# transmitter.net
KiCad netlist of a schematic drawn in EAGLE
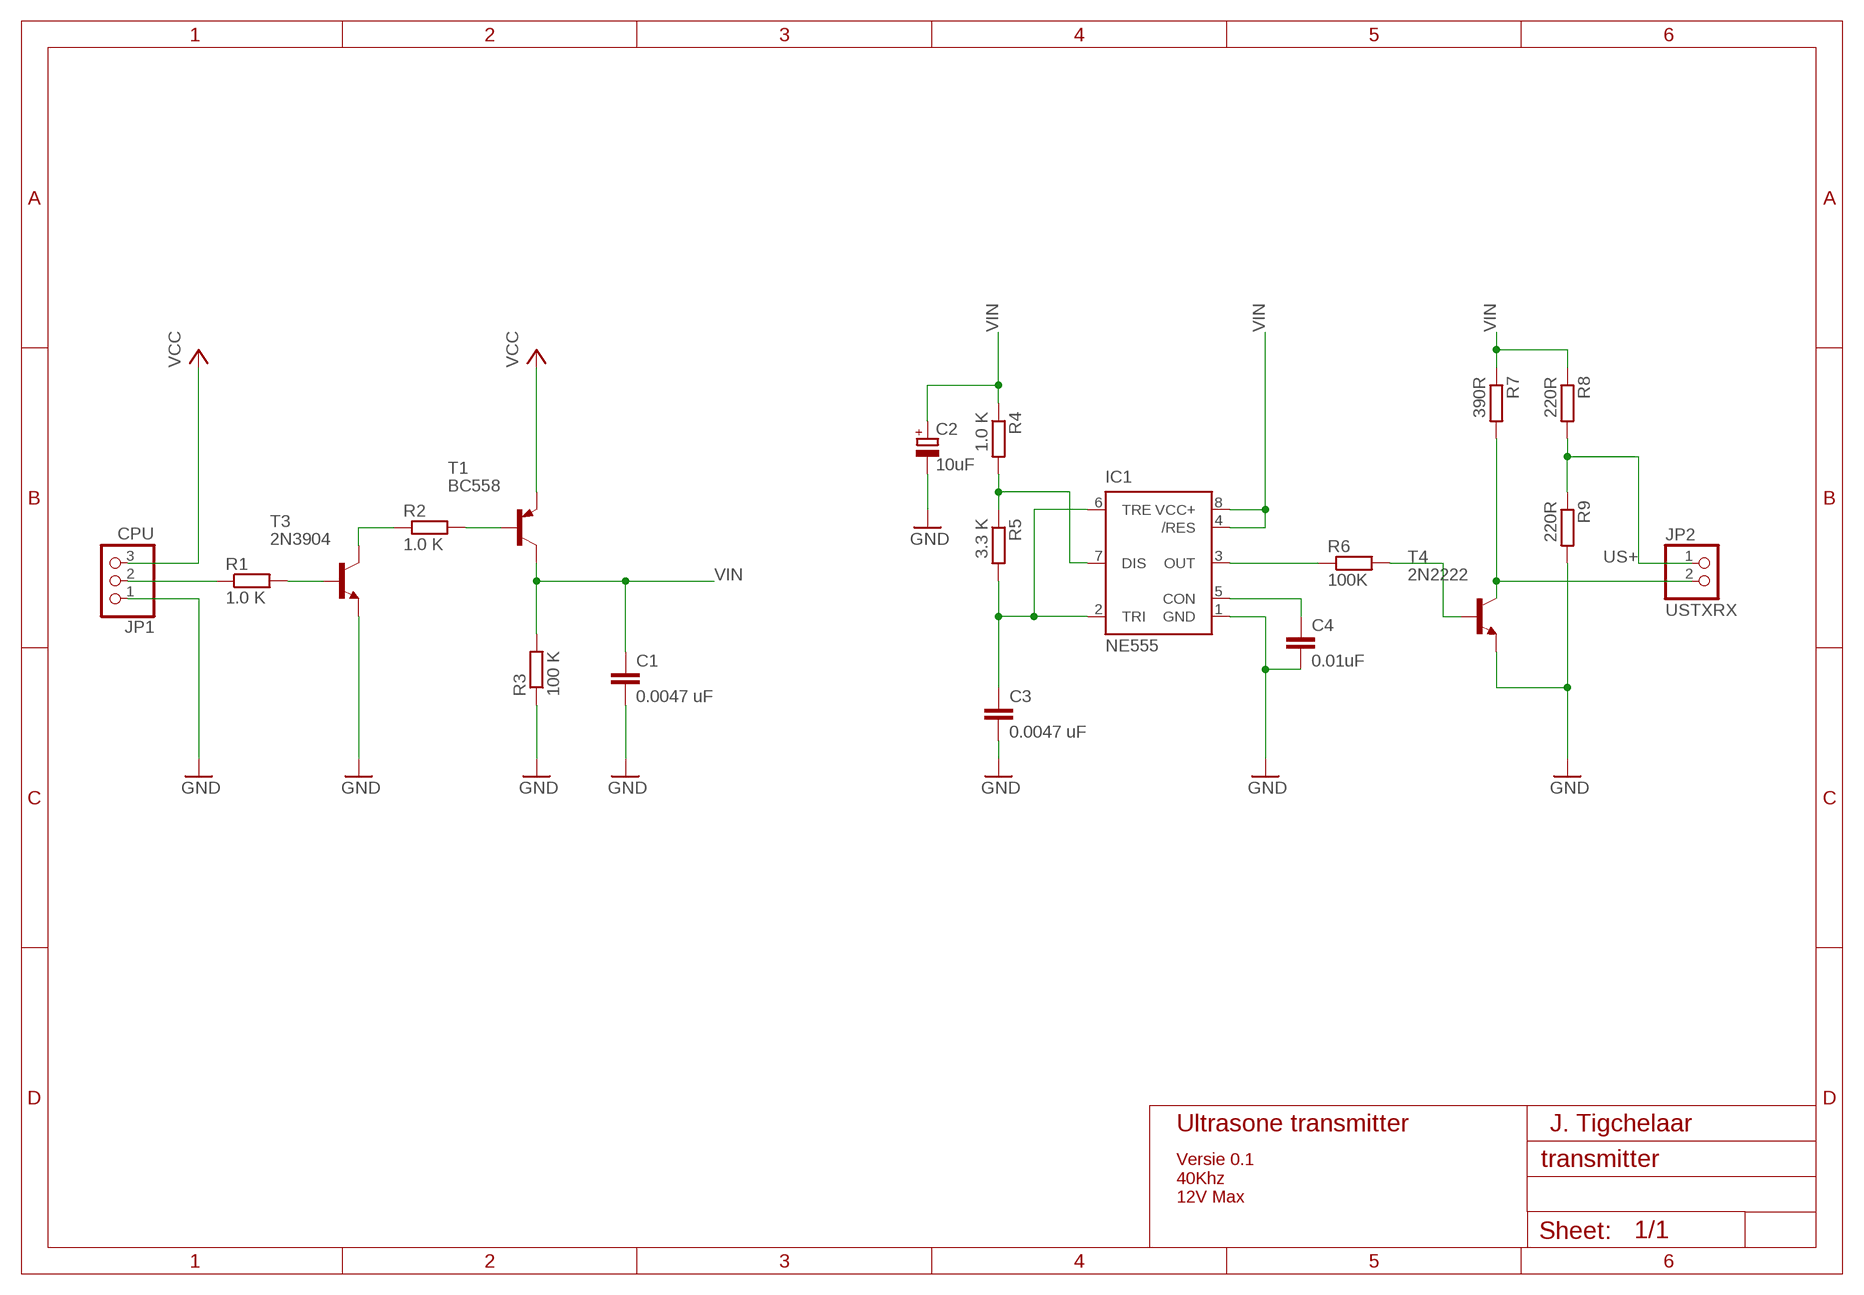
[diagram p0: schematic, sheet 1]

(export (version "E")
  (design (tool "Eeschema 10.0.6"))
  (components
    (comp (ref "C1")
      (value "0.0047 uF")
      (footprint "eagle-import:C025-025X050")
      (libsource (lib "eagle-import") (part "C-EU025-025X050"))
    )
    (comp (ref "C2")
      (value "10uF")
      (footprint "eagle-import:E5-5")
      (libsource (lib "eagle-import") (part "CPOL-EUE5-5"))
    )
    (comp (ref "C3")
      (value "0.0047 uF")
      (footprint "eagle-import:C025-025X050")
      (libsource (lib "eagle-import") (part "C-EU025-025X050"))
    )
    (comp (ref "C4")
      (value "0.01uF")
      (footprint "eagle-import:C025-025X050")
      (libsource (lib "eagle-import") (part "C-EU025-025X050"))
    )
    (comp (ref "IC1")
      (value "NE555")
      (footprint "eagle-import:DIL-08")
      (fields (field (name "MF") "Arrow Electronics") (field (name "MPN") "NE555N"))
      (libsource (lib "eagle-import") (part "NE555"))
    )
    (comp (ref "JP1")
      (value "CPU")
      (footprint "eagle-import:1X03")
      (libsource (lib "eagle-import") (part "PINHD-1X3"))
    )
    (comp (ref "JP2")
      (value "USTXRX")
      (footprint "eagle-import:1X02")
      (libsource (lib "eagle-import") (part "PINHD-1X2"))
    )
    (comp (ref "R1")
      (value "1.0 K")
      (footprint "eagle-import:0207_10")
      (libsource (lib "eagle-import") (part "R-EU_0207/10"))
    )
    (comp (ref "R2")
      (value "1.0 K")
      (footprint "eagle-import:0207_10")
      (libsource (lib "eagle-import") (part "R-EU_0207/10"))
    )
    (comp (ref "R3")
      (value "100 K")
      (footprint "eagle-import:0207_10")
      (libsource (lib "eagle-import") (part "R-EU_0207/10"))
    )
    (comp (ref "R4")
      (value "1.0 K")
      (footprint "eagle-import:0207_10")
      (libsource (lib "eagle-import") (part "R-EU_0207/10"))
    )
    (comp (ref "R5")
      (value "3.3 K")
      (footprint "eagle-import:0207_10")
      (libsource (lib "eagle-import") (part "R-EU_0207/10"))
    )
    (comp (ref "R6")
      (value "100K")
      (footprint "eagle-import:0207_10")
      (libsource (lib "eagle-import") (part "R-EU_0207/10"))
    )
    (comp (ref "R7")
      (value "390R")
      (footprint "eagle-import:0207_10")
      (libsource (lib "eagle-import") (part "R-EU_0207/10"))
    )
    (comp (ref "R8")
      (value "220R")
      (footprint "eagle-import:0207_10")
      (libsource (lib "eagle-import") (part "R-EU_0207/10"))
    )
    (comp (ref "R9")
      (value "220R")
      (footprint "eagle-import:0207_10")
      (libsource (lib "eagle-import") (part "R-EU_0207/10"))
    )
    (comp (ref "T1")
      (value "BC558")
      (footprint "eagle-import:TO92-CBE")
      (libsource (lib "eagle-import") (part "-PNP-TO92-CBE2N4126"))
    )
    (comp (ref "T3")
      (value "2N3904")
      (footprint "eagle-import:TO92-EBC")
      (libsource (lib "eagle-import") (part "-NPN-TO92-EBC2N3904"))
    )
    (comp (ref "T4")
      (value "2N2222")
      (footprint "eagle-import:TO92-EBC")
      (libsource (lib "eagle-import") (part "-NPN-TO92-EBC2N2222"))
    )
  )
  (nets
    (net (code "1") (name "/US+") (class "Default")
      (node (ref "JP2") (pin "1") (pinfunction "1_1") (pintype "passive"))
      (node (ref "R8") (pin "2") (pinfunction "2_2") (pintype "passive"))
      (node (ref "R9") (pin "1") (pinfunction "1_1") (pintype "passive"))
    )
    (net (code "2") (name "/VIN") (class "Default")
      (node (ref "C1") (pin "1") (pinfunction "1_1") (pintype "passive"))
      (node (ref "C2") (pin "+") (pinfunction "+_+") (pintype "passive"))
      (node (ref "IC1") (pin "4") (pinfunction "/RES_4") (pintype "input"))
      (node (ref "IC1") (pin "8") (pinfunction "VCC+_8") (pintype "power_in"))
      (node (ref "R3") (pin "2") (pinfunction "2_2") (pintype "passive"))
      (node (ref "R4") (pin "1") (pinfunction "1_1") (pintype "passive"))
      (node (ref "R7") (pin "1") (pinfunction "1_1") (pintype "passive"))
      (node (ref "R8") (pin "1") (pinfunction "1_1") (pintype "passive"))
      (node (ref "T1") (pin "C") (pinfunction "C_C") (pintype "passive"))
    )
    (net (code "3") (name "GND") (class "Default")
      (node (ref "C1") (pin "2") (pinfunction "2_2") (pintype "passive"))
      (node (ref "C2") (pin "-") (pinfunction "-_-") (pintype "passive"))
      (node (ref "C3") (pin "2") (pinfunction "2_2") (pintype "passive"))
      (node (ref "C4") (pin "2") (pinfunction "2_2") (pintype "passive"))
      (node (ref "IC1") (pin "1") (pinfunction "GND_1") (pintype "power_in"))
      (node (ref "JP1") (pin "1") (pinfunction "1_1") (pintype "passive"))
      (node (ref "R3") (pin "1") (pinfunction "1_1") (pintype "passive"))
      (node (ref "R9") (pin "2") (pinfunction "2_2") (pintype "passive"))
      (node (ref "T3") (pin "E") (pinfunction "E_E") (pintype "passive"))
      (node (ref "T4") (pin "E") (pinfunction "E_E") (pintype "passive"))
    )
    (net (code "4") (name "Net-(IC1-CON)") (class "Default")
      (node (ref "C4") (pin "1") (pinfunction "1_1") (pintype "passive"))
      (node (ref "IC1") (pin "5") (pinfunction "CON_5") (pintype "input"))
    )
    (net (code "5") (name "Net-(IC1-DIS)") (class "Default")
      (node (ref "IC1") (pin "7") (pinfunction "DIS_7") (pintype "input"))
      (node (ref "R4") (pin "2") (pinfunction "2_2") (pintype "passive"))
      (node (ref "R5") (pin "1") (pinfunction "1_1") (pintype "passive"))
    )
    (net (code "6") (name "Net-(IC1-OUT)") (class "Default")
      (node (ref "IC1") (pin "3") (pinfunction "OUT_3") (pintype "output"))
      (node (ref "R6") (pin "1") (pinfunction "1_1") (pintype "passive"))
    )
    (net (code "7") (name "Net-(IC1-TRE)") (class "Default")
      (node (ref "C3") (pin "1") (pinfunction "1_1") (pintype "passive"))
      (node (ref "IC1") (pin "2") (pinfunction "TRI_2") (pintype "input"))
      (node (ref "IC1") (pin "6") (pinfunction "TRE_6") (pintype "input"))
      (node (ref "R5") (pin "2") (pinfunction "2_2") (pintype "passive"))
    )
    (net (code "8") (name "Net-(JP1-Pad2)") (class "Default")
      (node (ref "JP1") (pin "2") (pinfunction "2_2") (pintype "passive"))
      (node (ref "R1") (pin "1") (pinfunction "1_1") (pintype "passive"))
    )
    (net (code "9") (name "Net-(JP2-Pad2)") (class "Default")
      (node (ref "JP2") (pin "2") (pinfunction "2_2") (pintype "passive"))
      (node (ref "R7") (pin "2") (pinfunction "2_2") (pintype "passive"))
      (node (ref "T4") (pin "C") (pinfunction "C_C") (pintype "passive"))
    )
    (net (code "10") (name "Net-(R1-Pad2)") (class "Default")
      (node (ref "R1") (pin "2") (pinfunction "2_2") (pintype "passive"))
      (node (ref "T3") (pin "B") (pinfunction "B_B") (pintype "passive"))
    )
    (net (code "11") (name "Net-(R2-Pad1)") (class "Default")
      (node (ref "R2") (pin "1") (pinfunction "1_1") (pintype "passive"))
      (node (ref "T3") (pin "C") (pinfunction "C_C") (pintype "passive"))
    )
    (net (code "12") (name "Net-(R2-Pad2)") (class "Default")
      (node (ref "R2") (pin "2") (pinfunction "2_2") (pintype "passive"))
      (node (ref "T1") (pin "B") (pinfunction "B_B") (pintype "passive"))
    )
    (net (code "13") (name "Net-(R6-Pad2)") (class "Default")
      (node (ref "R6") (pin "2") (pinfunction "2_2") (pintype "passive"))
      (node (ref "T4") (pin "B") (pinfunction "B_B") (pintype "passive"))
    )
    (net (code "14") (name "VCC") (class "Default")
      (node (ref "JP1") (pin "3") (pinfunction "3_3") (pintype "passive"))
      (node (ref "T1") (pin "E") (pinfunction "E_E") (pintype "passive"))
    )
  )
)
